# control_rev_a.net
KiCad netlist of a schematic drawn in EAGLE
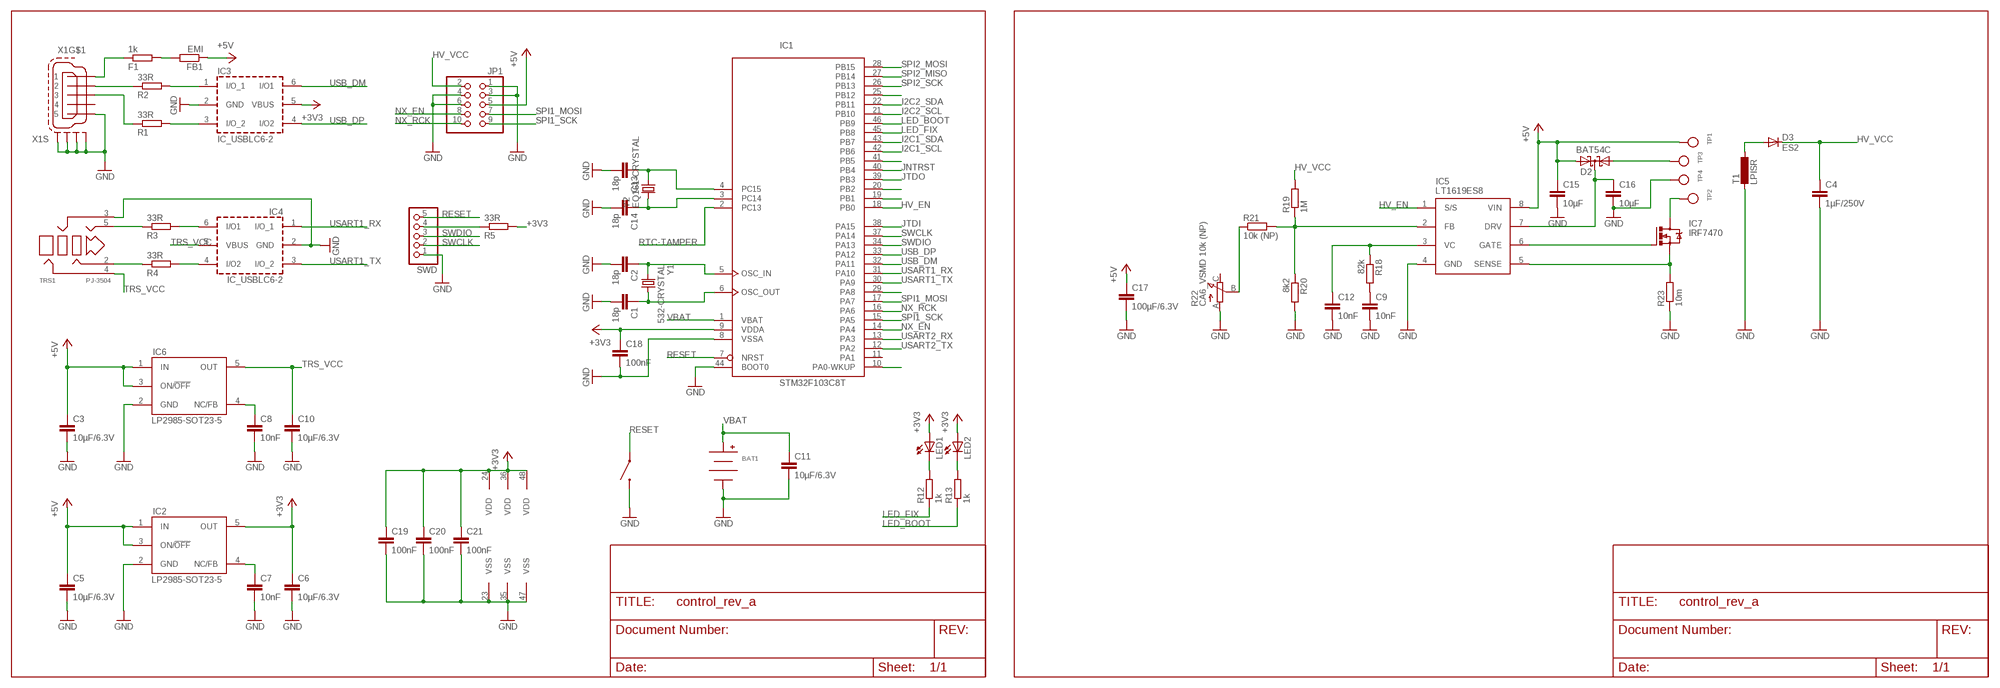
[diagram p0: schematic, sheet 1]

(export (version "E")
  (design (tool "Eeschema 10.0.6"))
  (components
    (comp (ref "BAT1")
      (value "CR1220-HOLDER")
      (footprint "eagle-import:HARWIN-CR1220")
      (libsource (lib "eagle-import") (part "CR1220-HOLDER"))
    )
    (comp (ref "C1")
      (value "18p")
      (footprint "eagle-import:C0603")
      (libsource (lib "eagle-import") (part "C-EUC0603"))
    )
    (comp (ref "C2")
      (value "18p")
      (footprint "eagle-import:C0603")
      (libsource (lib "eagle-import") (part "C-EUC0603"))
    )
    (comp (ref "C3")
      (value "10µF/6.3V")
      (footprint "eagle-import:C0603")
      (libsource (lib "eagle-import") (part "C-EUC0603"))
    )
    (comp (ref "C4")
      (value "1µF/250V")
      (footprint "eagle-import:C2220K")
      (libsource (lib "eagle-import") (part "C-EUC2220K"))
    )
    (comp (ref "C5")
      (value "10µF/6.3V")
      (footprint "eagle-import:C0603")
      (libsource (lib "eagle-import") (part "C-EUC0603"))
    )
    (comp (ref "C6")
      (value "10µF/6.3V")
      (footprint "eagle-import:C0603")
      (libsource (lib "eagle-import") (part "C-EUC0603"))
    )
    (comp (ref "C7")
      (value "10nF")
      (footprint "eagle-import:C0603")
      (libsource (lib "eagle-import") (part "C-EUC0603"))
    )
    (comp (ref "C8")
      (value "10nF")
      (footprint "eagle-import:C0603")
      (libsource (lib "eagle-import") (part "C-EUC0603"))
    )
    (comp (ref "C9")
      (value "10nF")
      (footprint "eagle-import:C0603")
      (libsource (lib "eagle-import") (part "C-EUC0603"))
    )
    (comp (ref "C10")
      (value "10µF/6.3V")
      (footprint "eagle-import:C0603")
      (libsource (lib "eagle-import") (part "C-EUC0603"))
    )
    (comp (ref "C11")
      (value "10µF/6.3V")
      (footprint "eagle-import:C0603")
      (libsource (lib "eagle-import") (part "C-EUC0603"))
    )
    (comp (ref "C12")
      (value "10nF")
      (footprint "eagle-import:C0603")
      (libsource (lib "eagle-import") (part "C-EUC0603"))
    )
    (comp (ref "C13")
      (value "18p")
      (footprint "eagle-import:C0603")
      (libsource (lib "eagle-import") (part "C-EUC0603"))
    )
    (comp (ref "C14")
      (value "18p")
      (footprint "eagle-import:C0603")
      (libsource (lib "eagle-import") (part "C-EUC0603"))
    )
    (comp (ref "C15")
      (value "10µF")
      (footprint "eagle-import:C0603")
      (libsource (lib "eagle-import") (part "C-EUC0603"))
    )
    (comp (ref "C16")
      (value "10µF")
      (footprint "eagle-import:C0603")
      (libsource (lib "eagle-import") (part "C-EUC0603"))
    )
    (comp (ref "C17")
      (value "100µF/6.3V")
      (footprint "eagle-import:C1210")
      (libsource (lib "eagle-import") (part "C-EUC1210"))
    )
    (comp (ref "C18")
      (value "100nF")
      (footprint "eagle-import:C0603")
      (libsource (lib "eagle-import") (part "C-EUC0603"))
    )
    (comp (ref "C19")
      (value "100nF")
      (footprint "eagle-import:C0603")
      (libsource (lib "eagle-import") (part "C-EUC0603"))
    )
    (comp (ref "C20")
      (value "100nF")
      (footprint "eagle-import:C0603")
      (libsource (lib "eagle-import") (part "C-EUC0603"))
    )
    (comp (ref "C21")
      (value "100nF")
      (footprint "eagle-import:C0603")
      (libsource (lib "eagle-import") (part "C-EUC0603"))
    )
    (comp (ref "D2")
      (value "BAT54C")
      (footprint "eagle-import:SOT23")
      (libsource (lib "eagle-import") (part "BAT54C"))
    )
    (comp (ref "D3")
      (value "ES2")
      (footprint "eagle-import:DO-214AA")
      (libsource (lib "eagle-import") (part "ES2"))
    )
    (comp (ref "F1")
      (value "1k")
      (footprint "eagle-import:R0603")
      (libsource (lib "eagle-import") (part "R-EU_R0603"))
    )
    (comp (ref "FB1")
      (value "EMI")
      (footprint "eagle-import:R0603")
      (libsource (lib "eagle-import") (part "R-EU_R0603"))
    )
    (comp (ref "IC1")
      (value "STM32F103C8T")
      (footprint "eagle-import:LQFP48")
      (libsource (lib "eagle-import") (part "STM32F103CT8"))
    )
    (comp (ref "IC2")
      (value "LP2985-SOT23-5")
      (footprint "eagle-import:SOT23-5")
      (libsource (lib "eagle-import") (part "LP2985-SOT23-5"))
    )
    (comp (ref "IC3")
      (value "IC_USBLC6-2")
      (footprint "eagle-import:SOT-23-6L")
      (libsource (lib "eagle-import") (part "IC_USBLC6-2"))
    )
    (comp (ref "IC4")
      (value "IC_USBLC6-2")
      (footprint "eagle-import:SOT-23-6L")
      (libsource (lib "eagle-import") (part "IC_USBLC6-2"))
    )
    (comp (ref "IC5")
      (value "LT1619ES8")
      (footprint "eagle-import:SO8")
      (libsource (lib "eagle-import") (part "LT1619ES8"))
    )
    (comp (ref "IC6")
      (value "LP2985-SOT23-5")
      (footprint "eagle-import:SOT23-5")
      (libsource (lib "eagle-import") (part "LP2985-SOT23-5"))
    )
    (comp (ref "IC7")
      (value "IRF7470")
      (footprint "eagle-import:SO8")
      (libsource (lib "eagle-import") (part "IRF7470"))
    )
    (comp (ref "ISP")
      (value "TACT-SWITCH-40-40")
      (footprint "eagle-import:40-40")
      (libsource (lib "eagle-import") (part "TACT-SWITCH-40-40"))
    )
    (comp (ref "JP1")
      (value "PINHD-2X5_2.54-SMD")
      (footprint "eagle-import:2X05SMD")
      (libsource (lib "eagle-import") (part "PINHD-2X5_2.54-SMD"))
    )
    (comp (ref "LED1")
      (value "LEDCHIP-LED0603")
      (footprint "eagle-import:CHIP-LED0603")
      (libsource (lib "eagle-import") (part "LEDCHIP-LED0603"))
    )
    (comp (ref "LED2")
      (value "LEDCHIP-LED0603")
      (footprint "eagle-import:CHIP-LED0603")
      (libsource (lib "eagle-import") (part "LEDCHIP-LED0603"))
    )
    (comp (ref "R1")
      (value "33R")
      (footprint "eagle-import:R0603")
      (libsource (lib "eagle-import") (part "R-EU_R0603"))
    )
    (comp (ref "R2")
      (value "33R")
      (footprint "eagle-import:R0603")
      (libsource (lib "eagle-import") (part "R-EU_R0603"))
    )
    (comp (ref "R3")
      (value "33R")
      (footprint "eagle-import:R0603")
      (libsource (lib "eagle-import") (part "R-EU_R0603"))
    )
    (comp (ref "R4")
      (value "33R")
      (footprint "eagle-import:R0603")
      (libsource (lib "eagle-import") (part "R-EU_R0603"))
    )
    (comp (ref "R5")
      (value "33R")
      (footprint "eagle-import:R0603")
      (libsource (lib "eagle-import") (part "R-EU_R0603"))
    )
    (comp (ref "R12")
      (value "1k")
      (footprint "eagle-import:R0603")
      (libsource (lib "eagle-import") (part "R-EU_R0603"))
    )
    (comp (ref "R13")
      (value "1k")
      (footprint "eagle-import:R0603")
      (libsource (lib "eagle-import") (part "R-EU_R0603"))
    )
    (comp (ref "R18")
      (value "82k")
      (footprint "eagle-import:R0603")
      (libsource (lib "eagle-import") (part "R-EU_R0603"))
    )
    (comp (ref "R19")
      (value "1M")
      (footprint "eagle-import:M1206")
      (libsource (lib "eagle-import") (part "R-EU_M1206"))
    )
    (comp (ref "R20")
      (value "8k2")
      (footprint "eagle-import:R0603")
      (libsource (lib "eagle-import") (part "R-EU_R0603"))
    )
    (comp (ref "R21")
      (value "10k (NP)")
      (footprint "eagle-import:R0603")
      (libsource (lib "eagle-import") (part "R-EU_R0603"))
    )
    (comp (ref "R22")
      (value "CA6_VSMD 10k (NP)")
      (footprint "eagle-import:CA6-VSMD")
      (libsource (lib "eagle-import") (part "CA6_VSMD"))
    )
    (comp (ref "R23")
      (value "10m")
      (footprint "eagle-import:R1206")
      (libsource (lib "eagle-import") (part "R-EU_R1206"))
    )
    (comp (ref "SWD")
      (value "HEADER-1X5ROUND")
      (footprint "eagle-import:1X05_ROUND")
      (libsource (lib "eagle-import") (part "HEADER-1X5ROUND"))
    )
    (comp (ref "T1")
      (value "LPISR")
      (footprint "eagle-import:PISR")
      (libsource (lib "eagle-import") (part "LPISR"))
    )
    (comp (ref "TP1")
      (value "TESTPOINTROUND2MM")
      (footprint "eagle-import:TESTPOINT_ROUND_2MM")
      (libsource (lib "eagle-import") (part "TESTPOINTROUND2MM"))
    )
    (comp (ref "TP2")
      (value "TESTPOINTROUND2MM")
      (footprint "eagle-import:TESTPOINT_ROUND_2MM")
      (libsource (lib "eagle-import") (part "TESTPOINTROUND2MM"))
    )
    (comp (ref "TP3")
      (value "TESTPOINTROUND2MM")
      (footprint "eagle-import:TESTPOINT_ROUND_2MM")
      (libsource (lib "eagle-import") (part "TESTPOINTROUND2MM"))
    )
    (comp (ref "TP4")
      (value "TESTPOINTROUND2MM")
      (footprint "eagle-import:TESTPOINT_ROUND_2MM")
      (libsource (lib "eagle-import") (part "TESTPOINTROUND2MM"))
    )
    (comp (ref "TRS1")
      (value "PJ-3504")
      (footprint "eagle-import:YD-PJ-3504")
      (libsource (lib "eagle-import") (part "PJ-3504"))
    )
    (comp (ref "X1")
      (value "MINI-USB-SCHIELD-32005-201")
      (footprint "eagle-import:32005-201")
      (libsource (lib "eagle-import") (part "MINI-USB-SCHIELD-32005-201"))
    )
    (comp (ref "Y1")
      (value "532-CRYSTAL")
      (footprint "eagle-import:2PIN50X32")
      (libsource (lib "eagle-import") (part "532-CRYSTAL"))
    )
    (comp (ref "Y2")
      (value "EQ161-CRYSTAL")
      (footprint "eagle-import:EQ161")
      (libsource (lib "eagle-import") (part "EQ161-CRYSTAL"))
    )
  )
  (nets
    (net (code "1") (name "+3V3") (class "Default")
      (node (ref "C18") (pin "1") (pinfunction "1_1") (pintype "passive"))
      (node (ref "C19") (pin "1") (pinfunction "1_1") (pintype "passive"))
      (node (ref "C20") (pin "1") (pinfunction "1_1") (pintype "passive"))
      (node (ref "C21") (pin "1") (pinfunction "1_1") (pintype "passive"))
      (node (ref "C6") (pin "1") (pinfunction "1_1") (pintype "passive"))
      (node (ref "IC1") (pin "24") (pinfunction "VDD_24") (pintype "power_in"))
      (node (ref "IC1") (pin "36") (pinfunction "VDD_36") (pintype "power_in"))
      (node (ref "IC1") (pin "48") (pinfunction "VDD_48") (pintype "power_in"))
      (node (ref "IC1") (pin "9") (pinfunction "VDDA_9") (pintype "power_in"))
      (node (ref "IC2") (pin "5") (pinfunction "OUT_5") (pintype "bidirectional"))
      (node (ref "IC3") (pin "5") (pinfunction "VBUS_5") (pintype "bidirectional"))
      (node (ref "LED1") (pin "A") (pinfunction "A_A") (pintype "passive"))
      (node (ref "LED2") (pin "A") (pinfunction "A_A") (pintype "passive"))
      (node (ref "R5") (pin "2") (pinfunction "2_2") (pintype "passive"))
    )
    (net (code "2") (name "+5V") (class "Default")
      (node (ref "C15") (pin "1") (pinfunction "1_1") (pintype "passive"))
      (node (ref "C17") (pin "1") (pinfunction "1_1") (pintype "passive"))
      (node (ref "C3") (pin "1") (pinfunction "1_1") (pintype "passive"))
      (node (ref "C5") (pin "1") (pinfunction "1_1") (pintype "passive"))
      (node (ref "D2") (pin "2") (pinfunction "A2_2") (pintype "passive"))
      (node (ref "FB1") (pin "1") (pinfunction "1_1") (pintype "passive"))
      (node (ref "IC2") (pin "1") (pinfunction "IN_1") (pintype "bidirectional"))
      (node (ref "IC2") (pin "3") (pinfunction "ON/~{OFF}_3") (pintype "bidirectional"))
      (node (ref "IC5") (pin "8") (pinfunction "VIN_8") (pintype "bidirectional"))
      (node (ref "IC6") (pin "1") (pinfunction "IN_1") (pintype "bidirectional"))
      (node (ref "IC6") (pin "3") (pinfunction "ON/~{OFF}_3") (pintype "bidirectional"))
      (node (ref "JP1") (pin "5") (pinfunction "5_5") (pintype "passive"))
      (node (ref "TP1") (pin "P$1") (pinfunction "P$1_P$1") (pintype "bidirectional"))
    )
    (net (code "3") (name "/HV_EN") (class "Default")
      (node (ref "IC1") (pin "18") (pinfunction "PB0_18") (pintype "bidirectional"))
      (node (ref "IC5") (pin "1") (pinfunction "S/S_1") (pintype "bidirectional"))
    )
    (net (code "4") (name "/HV_VCC") (class "Default")
      (node (ref "C4") (pin "1") (pinfunction "1_1") (pintype "passive"))
      (node (ref "D3") (pin "C") (pinfunction "C_C") (pintype "passive"))
      (node (ref "JP1") (pin "2") (pinfunction "2_2") (pintype "passive"))
      (node (ref "R19") (pin "2") (pinfunction "2_2") (pintype "passive"))
    )
    (net (code "5") (name "/I2C1_SCL") (class "Default")
      (node (ref "IC1") (pin "42") (pinfunction "PB6_42") (pintype "bidirectional"))
    )
    (net (code "6") (name "/I2C1_SDA") (class "Default")
      (node (ref "IC1") (pin "43") (pinfunction "PB7_43") (pintype "bidirectional"))
    )
    (net (code "7") (name "/I2C2_SCL") (class "Default")
      (node (ref "IC1") (pin "21") (pinfunction "PB10_21") (pintype "bidirectional"))
    )
    (net (code "8") (name "/I2C2_SDA") (class "Default")
      (node (ref "IC1") (pin "22") (pinfunction "PB11_22") (pintype "bidirectional"))
    )
    (net (code "9") (name "/JNTRST") (class "Default")
      (node (ref "IC1") (pin "40") (pinfunction "PB4_40") (pintype "bidirectional"))
    )
    (net (code "10") (name "/JTDI") (class "Default")
      (node (ref "IC1") (pin "38") (pinfunction "PA15_38") (pintype "bidirectional"))
    )
    (net (code "11") (name "/JTDO") (class "Default")
      (node (ref "IC1") (pin "39") (pinfunction "PB3_39") (pintype "bidirectional"))
    )
    (net (code "12") (name "/LED_BOOT") (class "Default")
      (node (ref "IC1") (pin "46") (pinfunction "PB9_46") (pintype "bidirectional"))
      (node (ref "R13") (pin "1") (pinfunction "1_1") (pintype "passive"))
    )
    (net (code "13") (name "/LED_FIX") (class "Default")
      (node (ref "IC1") (pin "45") (pinfunction "PB8_45") (pintype "bidirectional"))
      (node (ref "R12") (pin "1") (pinfunction "1_1") (pintype "passive"))
    )
    (net (code "14") (name "/NX_EN") (class "Default")
      (node (ref "IC1") (pin "14") (pinfunction "PA4_14") (pintype "bidirectional"))
      (node (ref "JP1") (pin "8") (pinfunction "8_8") (pintype "passive"))
    )
    (net (code "15") (name "/NX_RCK") (class "Default")
      (node (ref "IC1") (pin "16") (pinfunction "PA6_16") (pintype "bidirectional"))
      (node (ref "JP1") (pin "10") (pinfunction "10_10") (pintype "passive"))
    )
    (net (code "16") (name "/RESET") (class "Default")
      (node (ref "IC1") (pin "7") (pinfunction "NRST_7") (pintype "bidirectional"))
      (node (ref "ISP") (pin "3") (pinfunction "P$2_3") (pintype "bidirectional"))
      (node (ref "ISP") (pin "4") (pinfunction "P$2_4") (pintype "bidirectional"))
      (node (ref "SWD") (pin "5") (pinfunction "5_5") (pintype "passive"))
    )
    (net (code "17") (name "/RTC-TAMPER") (class "Default")
      (node (ref "IC1") (pin "2") (pinfunction "PC13_2") (pintype "bidirectional"))
    )
    (net (code "18") (name "/SPI1_MOSI") (class "Default")
      (node (ref "IC1") (pin "17") (pinfunction "PA7_17") (pintype "bidirectional"))
      (node (ref "JP1") (pin "7") (pinfunction "7_7") (pintype "passive"))
    )
    (net (code "19") (name "/SPI1_SCK") (class "Default")
      (node (ref "IC1") (pin "15") (pinfunction "PA5_15") (pintype "bidirectional"))
      (node (ref "JP1") (pin "9") (pinfunction "9_9") (pintype "passive"))
    )
    (net (code "20") (name "/SPI2_MISO") (class "Default")
      (node (ref "IC1") (pin "27") (pinfunction "PB14_27") (pintype "bidirectional"))
    )
    (net (code "21") (name "/SPI2_MOSI") (class "Default")
      (node (ref "IC1") (pin "28") (pinfunction "PB15_28") (pintype "bidirectional"))
    )
    (net (code "22") (name "/SPI2_SCK") (class "Default")
      (node (ref "IC1") (pin "26") (pinfunction "PB13_26") (pintype "bidirectional"))
    )
    (net (code "23") (name "/SWCLK") (class "Default")
      (node (ref "IC1") (pin "37") (pinfunction "PA14_37") (pintype "bidirectional"))
      (node (ref "SWD") (pin "2") (pinfunction "2_2") (pintype "passive"))
    )
    (net (code "24") (name "/SWDIO") (class "Default")
      (node (ref "IC1") (pin "34") (pinfunction "PA13_34") (pintype "bidirectional"))
      (node (ref "SWD") (pin "3") (pinfunction "3_3") (pintype "passive"))
    )
    (net (code "25") (name "/TRS_VCC") (class "Default")
      (node (ref "C10") (pin "1") (pinfunction "1_1") (pintype "passive"))
      (node (ref "IC4") (pin "5") (pinfunction "VBUS_5") (pintype "bidirectional"))
      (node (ref "IC6") (pin "5") (pinfunction "OUT_5") (pintype "bidirectional"))
      (node (ref "TRS1") (pin "4") (pinfunction "4_4") (pintype "bidirectional"))
    )
    (net (code "26") (name "/USART1_RX") (class "Default")
      (node (ref "IC1") (pin "31") (pinfunction "PA10_31") (pintype "bidirectional"))
      (node (ref "IC4") (pin "1") (pinfunction "I/O_1_1") (pintype "bidirectional"))
    )
    (net (code "27") (name "/USART1_TX") (class "Default")
      (node (ref "IC1") (pin "30") (pinfunction "PA9_30") (pintype "bidirectional"))
      (node (ref "IC4") (pin "3") (pinfunction "I/O_2_3") (pintype "bidirectional"))
    )
    (net (code "28") (name "/USART2_RX") (class "Default")
      (node (ref "IC1") (pin "13") (pinfunction "PA3_13") (pintype "bidirectional"))
    )
    (net (code "29") (name "/USART2_TX") (class "Default")
      (node (ref "IC1") (pin "12") (pinfunction "PA2_12") (pintype "bidirectional"))
    )
    (net (code "30") (name "/USB_DM") (class "Default")
      (node (ref "IC1") (pin "32") (pinfunction "PA11_32") (pintype "bidirectional"))
      (node (ref "IC3") (pin "6") (pinfunction "I/O1_6") (pintype "bidirectional"))
    )
    (net (code "31") (name "/USB_DP") (class "Default")
      (node (ref "IC1") (pin "33") (pinfunction "PA12_33") (pintype "bidirectional"))
      (node (ref "IC3") (pin "4") (pinfunction "I/O2_4") (pintype "bidirectional"))
    )
    (net (code "32") (name "/VBAT") (class "Default")
      (node (ref "BAT1") (pin "POS") (pinfunction "POS_POS") (pintype "bidirectional"))
      (node (ref "C11") (pin "1") (pinfunction "1_1") (pintype "passive"))
      (node (ref "IC1") (pin "1") (pinfunction "VBAT_1") (pintype "power_in"))
    )
    (net (code "33") (name "GND") (class "Default")
      (node (ref "BAT1") (pin "NEG") (pinfunction "NEG_NEG") (pintype "bidirectional"))
      (node (ref "C1") (pin "2") (pinfunction "2_2") (pintype "passive"))
      (node (ref "C10") (pin "2") (pinfunction "2_2") (pintype "passive"))
      (node (ref "C11") (pin "2") (pinfunction "2_2") (pintype "passive"))
      (node (ref "C12") (pin "2") (pinfunction "2_2") (pintype "passive"))
      (node (ref "C13") (pin "2") (pinfunction "2_2") (pintype "passive"))
      (node (ref "C14") (pin "2") (pinfunction "2_2") (pintype "passive"))
      (node (ref "C15") (pin "2") (pinfunction "2_2") (pintype "passive"))
      (node (ref "C16") (pin "2") (pinfunction "2_2") (pintype "passive"))
      (node (ref "C17") (pin "2") (pinfunction "2_2") (pintype "passive"))
      (node (ref "C18") (pin "2") (pinfunction "2_2") (pintype "passive"))
      (node (ref "C19") (pin "2") (pinfunction "2_2") (pintype "passive"))
      (node (ref "C2") (pin "2") (pinfunction "2_2") (pintype "passive"))
      (node (ref "C20") (pin "2") (pinfunction "2_2") (pintype "passive"))
      (node (ref "C21") (pin "2") (pinfunction "2_2") (pintype "passive"))
      (node (ref "C3") (pin "2") (pinfunction "2_2") (pintype "passive"))
      (node (ref "C4") (pin "2") (pinfunction "2_2") (pintype "passive"))
      (node (ref "C5") (pin "2") (pinfunction "2_2") (pintype "passive"))
      (node (ref "C6") (pin "2") (pinfunction "2_2") (pintype "passive"))
      (node (ref "C7") (pin "2") (pinfunction "2_2") (pintype "passive"))
      (node (ref "C8") (pin "2") (pinfunction "2_2") (pintype "passive"))
      (node (ref "C9") (pin "2") (pinfunction "2_2") (pintype "passive"))
      (node (ref "IC1") (pin "23") (pinfunction "VSS_23") (pintype "power_in"))
      (node (ref "IC1") (pin "35") (pinfunction "VSS_35") (pintype "power_in"))
      (node (ref "IC1") (pin "44") (pinfunction "BOOT0_44") (pintype "input"))
      (node (ref "IC1") (pin "47") (pinfunction "VSS_47") (pintype "power_in"))
      (node (ref "IC1") (pin "8") (pinfunction "VSSA_8") (pintype "power_in"))
      (node (ref "IC2") (pin "2") (pinfunction "GND_2") (pintype "bidirectional"))
      (node (ref "IC3") (pin "2") (pinfunction "GND_2") (pintype "bidirectional"))
      (node (ref "IC4") (pin "2") (pinfunction "GND_2") (pintype "bidirectional"))
      (node (ref "IC5") (pin "4") (pinfunction "GND_4") (pintype "bidirectional"))
      (node (ref "IC6") (pin "2") (pinfunction "GND_2") (pintype "bidirectional"))
      (node (ref "ISP") (pin "1") (pinfunction "P$1_1") (pintype "bidirectional"))
      (node (ref "ISP") (pin "2") (pinfunction "P$1_2") (pintype "bidirectional"))
      (node (ref "JP1") (pin "1") (pinfunction "1_1") (pintype "passive"))
      (node (ref "JP1") (pin "3") (pinfunction "3_3") (pintype "passive"))
      (node (ref "JP1") (pin "4") (pinfunction "4_4") (pintype "passive"))
      (node (ref "JP1") (pin "6") (pinfunction "6_6") (pintype "passive"))
      (node (ref "R20") (pin "2") (pinfunction "2_2") (pintype "passive"))
      (node (ref "R22") (pin "A") (pinfunction "A_A") (pintype "passive"))
      (node (ref "R23") (pin "1") (pinfunction "1_1") (pintype "passive"))
      (node (ref "SWD") (pin "1") (pinfunction "1_1") (pintype "passive"))
      (node (ref "T1") (pin "P$2") (pinfunction "2_P$2") (pintype "passive"))
      (node (ref "TP4") (pin "P$1") (pinfunction "P$1_P$1") (pintype "bidirectional"))
      (node (ref "TRS1") (pin "3") (pinfunction "3_3") (pintype "bidirectional"))
      (node (ref "X1") (pin "5") (pinfunction "5_5") (pintype "passive"))
      (node (ref "X1") (pin "M1") (pinfunction "S1_M1") (pintype "passive"))
      (node (ref "X1") (pin "M2") (pinfunction "S2_M2") (pintype "passive"))
      (node (ref "X1") (pin "M3") (pinfunction "S3_M3") (pintype "passive"))
      (node (ref "X1") (pin "M4") (pinfunction "S4_M4") (pintype "passive"))
    )
    (net (code "34") (name "Net-(C9-Pad1)") (class "Default")
      (node (ref "C9") (pin "1") (pinfunction "1_1") (pintype "passive"))
      (node (ref "R18") (pin "2") (pinfunction "2_2") (pintype "passive"))
    )
    (net (code "35") (name "Net-(D2-A1)") (class "Default")
      (node (ref "D2") (pin "1") (pinfunction "A1_1") (pintype "passive"))
      (node (ref "TP3") (pin "P$1") (pinfunction "P$1_P$1") (pintype "bidirectional"))
    )
    (net (code "36") (name "Net-(D2-CC)") (class "Default")
      (node (ref "C16") (pin "1") (pinfunction "1_1") (pintype "passive"))
      (node (ref "D2") (pin "3") (pinfunction "CC_3") (pintype "passive"))
      (node (ref "IC5") (pin "7") (pinfunction "DRV_7") (pintype "bidirectional"))
    )
    (net (code "37") (name "Net-(F1-Pad1)") (class "Default")
      (node (ref "F1") (pin "1") (pinfunction "1_1") (pintype "passive"))
      (node (ref "X1") (pin "1") (pinfunction "1_1") (pintype "passive"))
    )
    (net (code "38") (name "Net-(F1-Pad2)") (class "Default")
      (node (ref "F1") (pin "2") (pinfunction "2_2") (pintype "passive"))
      (node (ref "FB1") (pin "2") (pinfunction "2_2") (pintype "passive"))
    )
    (net (code "39") (name "Net-(IC1A-OSC_IN)") (class "Default")
      (node (ref "C2") (pin "1") (pinfunction "1_1") (pintype "passive"))
      (node (ref "IC1") (pin "5") (pinfunction "OSC_IN_5") (pintype "bidirectional"))
      (node (ref "Y1") (pin "P$2") (pinfunction "2_P$2") (pintype "passive"))
    )
    (net (code "40") (name "Net-(IC1A-OSC_OUT)") (class "Default")
      (node (ref "C1") (pin "1") (pinfunction "1_1") (pintype "passive"))
      (node (ref "IC1") (pin "6") (pinfunction "OSC_OUT_6") (pintype "bidirectional"))
      (node (ref "Y1") (pin "P$1") (pinfunction "1_P$1") (pintype "passive"))
    )
    (net (code "41") (name "Net-(IC1A-PC14)") (class "Default")
      (node (ref "C14") (pin "1") (pinfunction "1_1") (pintype "passive"))
      (node (ref "IC1") (pin "3") (pinfunction "PC14_3") (pintype "bidirectional"))
      (node (ref "Y2") (pin "P$2") (pinfunction "2_P$2") (pintype "passive"))
    )
    (net (code "42") (name "Net-(IC1A-PC15)") (class "Default")
      (node (ref "C13") (pin "1") (pinfunction "1_1") (pintype "passive"))
      (node (ref "IC1") (pin "4") (pinfunction "PC15_4") (pintype "bidirectional"))
      (node (ref "Y2") (pin "P$1") (pinfunction "1_P$1") (pintype "passive"))
    )
    (net (code "43") (name "Net-(IC2-NC{slash}FB)") (class "Default")
      (node (ref "C7") (pin "1") (pinfunction "1_1") (pintype "passive"))
      (node (ref "IC2") (pin "4") (pinfunction "NC/FB_4") (pintype "bidirectional"))
    )
    (net (code "44") (name "Net-(IC3-I{slash}O_1)") (class "Default")
      (node (ref "IC3") (pin "1") (pinfunction "I/O_1_1") (pintype "bidirectional"))
      (node (ref "R2") (pin "2") (pinfunction "2_2") (pintype "passive"))
    )
    (net (code "45") (name "Net-(IC3-I{slash}O_2)") (class "Default")
      (node (ref "IC3") (pin "3") (pinfunction "I/O_2_3") (pintype "bidirectional"))
      (node (ref "R1") (pin "2") (pinfunction "2_2") (pintype "passive"))
    )
    (net (code "46") (name "Net-(IC4-I{slash}O1)") (class "Default")
      (node (ref "IC4") (pin "6") (pinfunction "I/O1_6") (pintype "bidirectional"))
      (node (ref "R3") (pin "2") (pinfunction "2_2") (pintype "passive"))
    )
    (net (code "47") (name "Net-(IC4-I{slash}O2)") (class "Default")
      (node (ref "IC4") (pin "4") (pinfunction "I/O2_4") (pintype "bidirectional"))
      (node (ref "R4") (pin "2") (pinfunction "2_2") (pintype "passive"))
    )
    (net (code "48") (name "Net-(IC5-FB)") (class "Default")
      (node (ref "IC5") (pin "2") (pinfunction "FB_2") (pintype "bidirectional"))
      (node (ref "R19") (pin "1") (pinfunction "1_1") (pintype "passive"))
      (node (ref "R20") (pin "1") (pinfunction "1_1") (pintype "passive"))
      (node (ref "R21") (pin "2") (pinfunction "2_2") (pintype "passive"))
    )
    (net (code "49") (name "Net-(IC5-GATE)") (class "Default")
      (node (ref "IC5") (pin "6") (pinfunction "GATE_6") (pintype "bidirectional"))
      (node (ref "IC7") (pin "4") (pinfunction "G_4") (pintype "passive"))
    )
    (net (code "50") (name "Net-(IC5-SENSE)") (class "Default")
      (node (ref "IC5") (pin "5") (pinfunction "SENSE_5") (pintype "bidirectional"))
      (node (ref "IC7") (pin "1") (pinfunction "S_1") (pintype "passive"))
      (node (ref "IC7") (pin "2") (pinfunction "S_2") (pintype "passive"))
      (node (ref "IC7") (pin "3") (pinfunction "S_3") (pintype "passive"))
      (node (ref "R23") (pin "2") (pinfunction "2_2") (pintype "passive"))
    )
    (net (code "51") (name "Net-(IC5-VC)") (class "Default")
      (node (ref "C12") (pin "1") (pinfunction "1_1") (pintype "passive"))
      (node (ref "IC5") (pin "3") (pinfunction "VC_3") (pintype "bidirectional"))
      (node (ref "R18") (pin "1") (pinfunction "1_1") (pintype "passive"))
    )
    (net (code "52") (name "Net-(IC6-NC{slash}FB)") (class "Default")
      (node (ref "C8") (pin "1") (pinfunction "1_1") (pintype "passive"))
      (node (ref "IC6") (pin "4") (pinfunction "NC/FB_4") (pintype "bidirectional"))
    )
    (net (code "53") (name "Net-(IC7-D-Pad5)") (class "Default")
      (node (ref "IC7") (pin "5") (pinfunction "D_5") (pintype "passive"))
      (node (ref "IC7") (pin "6") (pinfunction "D_6") (pintype "passive"))
      (node (ref "IC7") (pin "7") (pinfunction "D_7") (pintype "passive"))
      (node (ref "IC7") (pin "8") (pinfunction "D_8") (pintype "passive"))
      (node (ref "TP2") (pin "P$1") (pinfunction "P$1_P$1") (pintype "bidirectional"))
    )
    (net (code "54") (name "Net-(LED1-PadC)") (class "Default")
      (node (ref "LED1") (pin "C") (pinfunction "C_C") (pintype "passive"))
      (node (ref "R12") (pin "2") (pinfunction "2_2") (pintype "passive"))
    )
    (net (code "55") (name "Net-(LED2-PadC)") (class "Default")
      (node (ref "LED2") (pin "C") (pinfunction "C_C") (pintype "passive"))
      (node (ref "R13") (pin "2") (pinfunction "2_2") (pintype "passive"))
    )
    (net (code "56") (name "Net-(R1-Pad1)") (class "Default")
      (node (ref "R1") (pin "1") (pinfunction "1_1") (pintype "passive"))
      (node (ref "X1") (pin "3") (pinfunction "3_3") (pintype "passive"))
    )
    (net (code "57") (name "Net-(R2-Pad1)") (class "Default")
      (node (ref "R2") (pin "1") (pinfunction "1_1") (pintype "passive"))
      (node (ref "X1") (pin "2") (pinfunction "2_2") (pintype "passive"))
    )
    (net (code "58") (name "Net-(R3-Pad1)") (class "Default")
      (node (ref "R3") (pin "1") (pinfunction "1_1") (pintype "passive"))
      (node (ref "TRS1") (pin "5") (pinfunction "5_5") (pintype "bidirectional"))
    )
    (net (code "59") (name "Net-(R4-Pad1)") (class "Default")
      (node (ref "R4") (pin "1") (pinfunction "1_1") (pintype "passive"))
      (node (ref "TRS1") (pin "2") (pinfunction "2_2") (pintype "bidirectional"))
    )
    (net (code "60") (name "Net-(R5-Pad1)") (class "Default")
      (node (ref "R5") (pin "1") (pinfunction "1_1") (pintype "passive"))
      (node (ref "SWD") (pin "4") (pinfunction "4_4") (pintype "passive"))
    )
    (net (code "61") (name "Net-(R22-S)") (class "Default")
      (node (ref "R21") (pin "1") (pinfunction "1_1") (pintype "passive"))
      (node (ref "R22") (pin "B") (pinfunction "S_B") (pintype "passive"))
    )
    (net (code "62") (name "Net-(T1-1)") (class "Default")
      (node (ref "D3") (pin "A") (pinfunction "A_A") (pintype "passive"))
      (node (ref "T1") (pin "P$1") (pinfunction "1_P$1") (pintype "passive"))
    )
    (net (code "63") (name "unconnected-(IC1A-PA0-WKUP-Pad10)") (class "Default")
      (node (ref "IC1") (pin "10") (pinfunction "PA0-WKUP_10") (pintype "bidirectional"))
    )
    (net (code "64") (name "unconnected-(IC1A-PA1-Pad11)") (class "Default")
      (node (ref "IC1") (pin "11") (pinfunction "PA1_11") (pintype "bidirectional"))
    )
    (net (code "65") (name "unconnected-(IC1A-PA8-Pad29)") (class "Default")
      (node (ref "IC1") (pin "29") (pinfunction "PA8_29") (pintype "bidirectional"))
    )
    (net (code "66") (name "unconnected-(IC1A-PB1-Pad19)") (class "Default")
      (node (ref "IC1") (pin "19") (pinfunction "PB1_19") (pintype "bidirectional"))
    )
    (net (code "67") (name "unconnected-(IC1A-PB2-Pad20)") (class "Default")
      (node (ref "IC1") (pin "20") (pinfunction "PB2_20") (pintype "bidirectional"))
    )
    (net (code "68") (name "unconnected-(IC1A-PB5-Pad41)") (class "Default")
      (node (ref "IC1") (pin "41") (pinfunction "PB5_41") (pintype "bidirectional"))
    )
    (net (code "69") (name "unconnected-(IC1A-PB12-Pad25)") (class "Default")
      (node (ref "IC1") (pin "25") (pinfunction "PB12_25") (pintype "bidirectional"))
    )
    (net (code "70") (name "unconnected-(R22-E-PadC)") (class "Default")
      (node (ref "R22") (pin "C") (pinfunction "E_C") (pintype "passive"))
    )
    (net (code "71") (name "unconnected-(X1-Pad4)") (class "Default")
      (node (ref "X1") (pin "4") (pinfunction "4_4") (pintype "passive"))
    )
  )
)
